# lab1_kozlov_usb_spi.net
KiCad netlist of a schematic drawn in Altium Designer
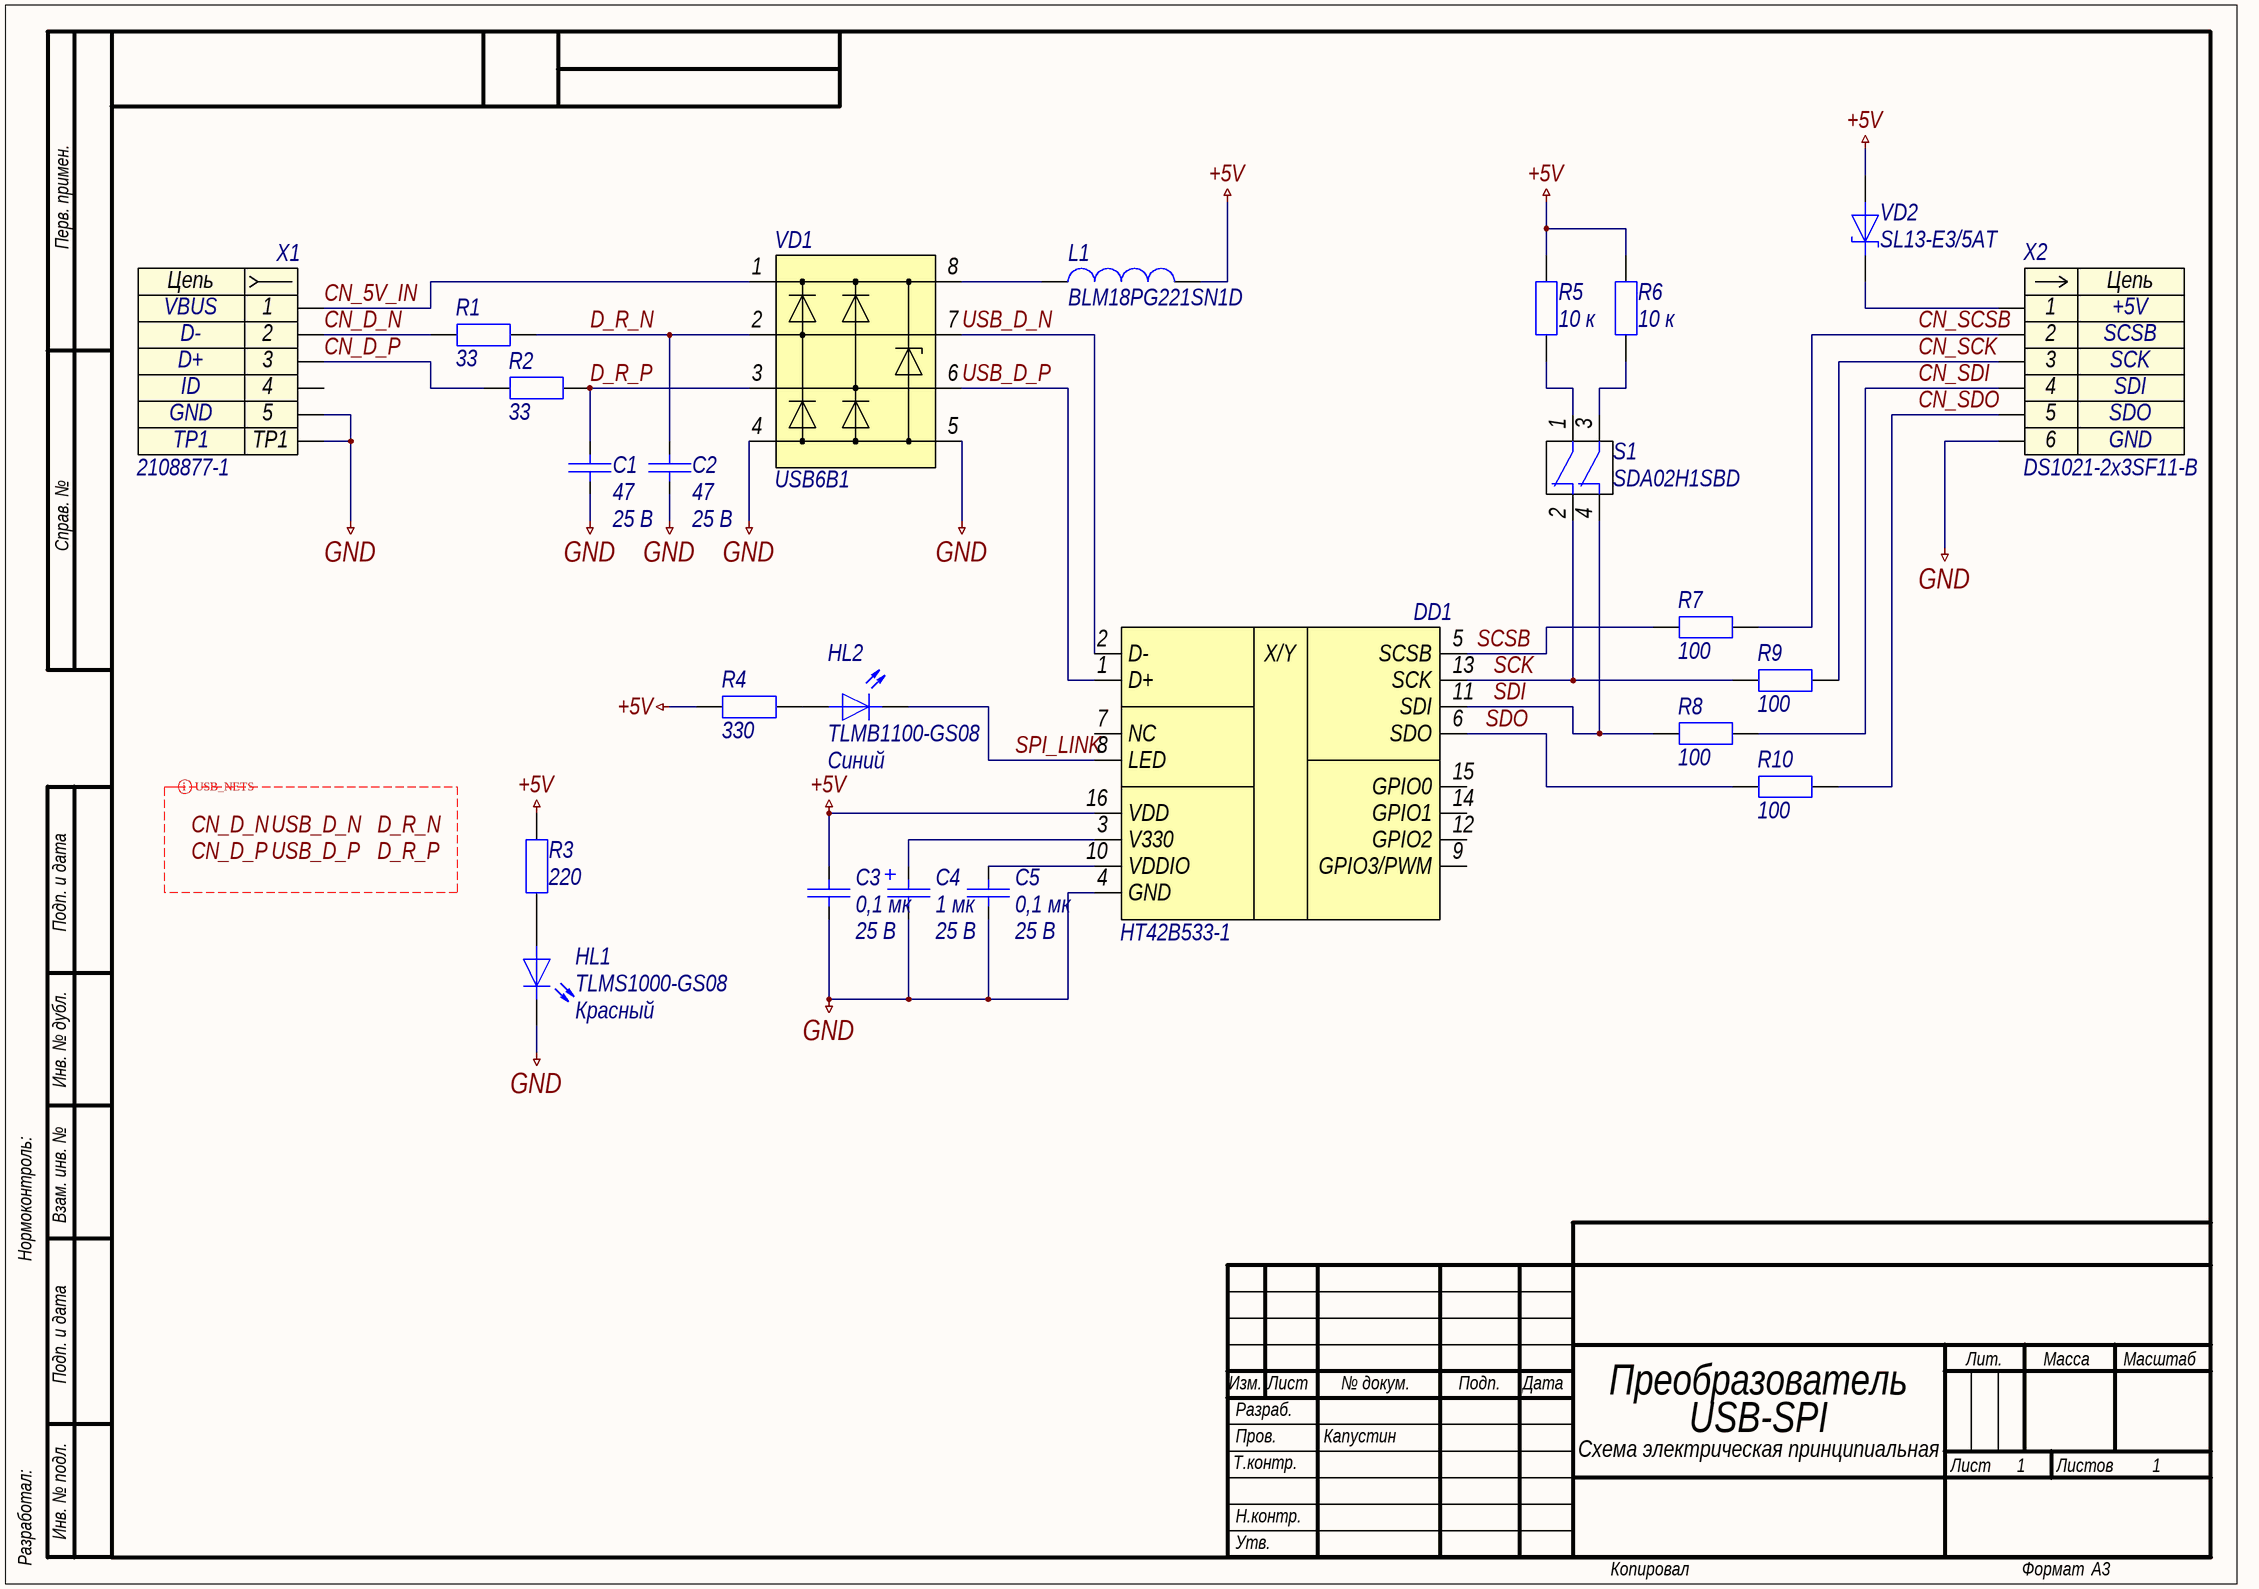
[diagram p0: lab1_kozlov_usb_spi.SchDoc]

(export (version "E")
  (design (tool "Eeschema 10.0.6"))
  (components
    (comp (ref "C1")
      (value "47")
      (footprint "C0201")
      (description "=Описание")
      (fields (field (name "НАПРЯЖЕНИЕ") "25 В"))
      (libsource (lib "Database_Students") (part "CAPACITOR-NONPOLAR"))
    )
    (comp (ref "C2")
      (value "47")
      (footprint "C0201")
      (description "=Описание")
      (fields (field (name "НАПРЯЖЕНИЕ") "25 В"))
      (libsource (lib "Database_Students") (part "CAPACITOR-NONPOLAR"))
    )
    (comp (ref "C3")
      (value "0,1 мк")
      (footprint "C0603")
      (description "=Описание")
      (fields (field (name "НАПРЯЖЕНИЕ") "25 В"))
      (libsource (lib "Database_Students") (part "CAPACITOR-NONPOLAR"))
    )
    (comp (ref "C4")
      (value "1 мк")
      (footprint "C1206POLAR")
      (description "=Описание")
      (fields (field (name "НАПРЯЖЕНИЕ") "25 В"))
      (libsource (lib "Database_Students") (part "CAPACITOR-POLAR"))
    )
    (comp (ref "C5")
      (value "0,1 мк")
      (footprint "C0603")
      (description "=Описание")
      (fields (field (name "НАПРЯЖЕНИЕ") "25 В"))
      (libsource (lib "Database_Students") (part "CAPACITOR-NONPOLAR"))
    )
    (comp (ref "DD1")
      (value "HT42B533-1")
      (footprint "SOP-16")
      (description "=Описание")
      (libsource (lib "Database_Students") (part "HT42B533-1"))
    )
    (comp (ref "HL1")
      (value "TLMS1000-GS08")
      (footprint "HL0603")
      (description "=Описание")
      (fields (field (name "COLOUR") "Красный"))
      (libsource (lib "Database_Students") (part "LED-COMMON"))
    )
    (comp (ref "HL2")
      (value "TLMB1100-GS08")
      (footprint "HL0603")
      (description "=Описание")
      (fields (field (name "COLOUR") "Синий"))
      (libsource (lib "Database_Students") (part "LED-COMMON"))
    )
    (comp (ref "L1")
      (value "BLM18PG221SN1D")
      (footprint "BLM-2-0603")
      (description "=Описание")
      (libsource (lib "Database_Students") (part "FERRITE-BEAD"))
    )
    (comp (ref "R1")
      (value "33")
      (footprint "R0603")
      (description "=Описание")
      (libsource (lib "Database_Students") (part "R-COMMON"))
    )
    (comp (ref "R2")
      (value "33")
      (footprint "R0603")
      (description "=Описание")
      (libsource (lib "Database_Students") (part "R-COMMON"))
    )
    (comp (ref "R3")
      (value "220")
      (footprint "R0603")
      (description "=Описание")
      (libsource (lib "Database_Students") (part "R-COMMON"))
    )
    (comp (ref "R4")
      (value "330")
      (footprint "R0603")
      (description "=Описание")
      (libsource (lib "Database_Students") (part "R-COMMON"))
    )
    (comp (ref "R5")
      (value "10 к")
      (footprint "R0603")
      (description "=Описание")
      (libsource (lib "Database_Students") (part "R-COMMON"))
    )
    (comp (ref "R6")
      (value "10 к")
      (footprint "R0603")
      (description "=Описание")
      (libsource (lib "Database_Students") (part "R-COMMON"))
    )
    (comp (ref "R7")
      (value "100")
      (footprint "R0603")
      (description "=Описание")
      (libsource (lib "Database_Students") (part "R-COMMON"))
    )
    (comp (ref "R8")
      (value "100")
      (footprint "R0603")
      (description "=Описание")
      (libsource (lib "Database_Students") (part "R-COMMON"))
    )
    (comp (ref "R9")
      (value "100")
      (footprint "R0603")
      (description "=Описание")
      (libsource (lib "Database_Students") (part "R-COMMON"))
    )
    (comp (ref "R10")
      (value "100")
      (footprint "R0603")
      (description "=Описание")
      (libsource (lib "Database_Students") (part "R-COMMON"))
    )
    (comp (ref "S1")
      (value "SDA02H1SBD")
      (footprint "SDA02H1SBD")
      (description "=Описание")
      (libsource (lib "Database_Students") (part "SWITCH-4C"))
    )
    (comp (ref "VD1")
      (value "USB6B1")
      (footprint "SOIC-8")
      (description "=Описание")
      (libsource (lib "Database_Students") (part "USB6B1"))
    )
    (comp (ref "VD2")
      (value "SL13-E3/5AT")
      (footprint "DO-214AC")
      (description "=Описание")
      (libsource (lib "Database_Students") (part "DIODE-SCHOTTKY"))
    )
    (comp (ref "X1")
      (value "2108877-1")
      (footprint "2108877-1")
      (description "=Описание")
      (libsource (lib "Database_Students") (part "HEADER-5-TP1-SCT"))
    )
    (comp (ref "X2")
      (value "DS1021-2x3SF11-B")
      (footprint "DS1021-2X3SF11-B")
      (description "=Описание")
      (libsource (lib "Database_Students") (part "HEADER-6-PLG"))
    )
  )
  (nets
    (net (code "1") (name "+5V") (class "Default")
      (node (ref "C3") (pin "1") (pinfunction "1_1") (pintype "passive"))
      (node (ref "DD1") (pin "16") (pinfunction "VDD_16") (pintype "passive"))
      (node (ref "L1") (pin "2") (pinfunction "2_2") (pintype "passive"))
      (node (ref "R3") (pin "2") (pinfunction "2_2") (pintype "passive"))
      (node (ref "R4") (pin "1") (pinfunction "1_1") (pintype "passive"))
      (node (ref "R5") (pin "2") (pinfunction "2_2") (pintype "passive"))
      (node (ref "R6") (pin "2") (pinfunction "2_2") (pintype "passive"))
      (node (ref "VD2") (pin "2") (pinfunction "2_2") (pintype "passive"))
    )
    (net (code "2") (name "/CN_5V_IN") (class "Default")
      (node (ref "VD1") (pin "1") (pinfunction "1_1") (pintype "passive"))
      (node (ref "X1") (pin "1") (pinfunction "1_1") (pintype "passive"))
    )
    (net (code "3") (name "/CN_D_N") (class "Default")
      (node (ref "R1") (pin "1") (pinfunction "1_1") (pintype "passive"))
      (node (ref "X1") (pin "2") (pinfunction "2_2") (pintype "passive"))
    )
    (net (code "4") (name "/CN_D_P") (class "Default")
      (node (ref "R2") (pin "1") (pinfunction "1_1") (pintype "passive"))
      (node (ref "X1") (pin "3") (pinfunction "3_3") (pintype "passive"))
    )
    (net (code "5") (name "/CN_SCK") (class "Default")
      (node (ref "R9") (pin "2") (pinfunction "2_2") (pintype "passive"))
      (node (ref "X2") (pin "3") (pinfunction "3_3") (pintype "passive"))
    )
    (net (code "6") (name "/CN_SCSB") (class "Default")
      (node (ref "R7") (pin "2") (pinfunction "2_2") (pintype "passive"))
      (node (ref "X2") (pin "2") (pinfunction "2_2") (pintype "passive"))
    )
    (net (code "7") (name "/CN_SDI") (class "Default")
      (node (ref "R8") (pin "2") (pinfunction "2_2") (pintype "passive"))
      (node (ref "X2") (pin "4") (pinfunction "4_4") (pintype "passive"))
    )
    (net (code "8") (name "/CN_SDO") (class "Default")
      (node (ref "R10") (pin "2") (pinfunction "2_2") (pintype "passive"))
      (node (ref "X2") (pin "5") (pinfunction "5_5") (pintype "passive"))
    )
    (net (code "9") (name "/D_R_N") (class "Default")
      (node (ref "C2") (pin "1") (pinfunction "1_1") (pintype "passive"))
      (node (ref "R1") (pin "2") (pinfunction "2_2") (pintype "passive"))
      (node (ref "VD1") (pin "2") (pinfunction "2_2") (pintype "passive"))
    )
    (net (code "10") (name "/D_R_P") (class "Default")
      (node (ref "C1") (pin "1") (pinfunction "1_1") (pintype "passive"))
      (node (ref "R2") (pin "2") (pinfunction "2_2") (pintype "passive"))
      (node (ref "VD1") (pin "3") (pinfunction "3_3") (pintype "passive"))
    )
    (net (code "11") (name "/SCK") (class "Default")
      (node (ref "DD1") (pin "13") (pinfunction "SCK_13") (pintype "passive"))
      (node (ref "R9") (pin "1") (pinfunction "1_1") (pintype "passive"))
      (node (ref "S1") (pin "2") (pinfunction "2_2") (pintype "passive"))
    )
    (net (code "12") (name "/SCSB") (class "Default")
      (node (ref "DD1") (pin "5") (pinfunction "SCSB_5") (pintype "passive"))
      (node (ref "R7") (pin "1") (pinfunction "1_1") (pintype "passive"))
    )
    (net (code "13") (name "/SDI") (class "Default")
      (node (ref "DD1") (pin "11") (pinfunction "SDI_11") (pintype "passive"))
      (node (ref "R8") (pin "1") (pinfunction "1_1") (pintype "passive"))
      (node (ref "S1") (pin "4") (pinfunction "4_4") (pintype "passive"))
    )
    (net (code "14") (name "/SDO") (class "Default")
      (node (ref "DD1") (pin "6") (pinfunction "SDO_6") (pintype "passive"))
      (node (ref "R10") (pin "1") (pinfunction "1_1") (pintype "passive"))
    )
    (net (code "15") (name "/SPI_LINK") (class "Default")
      (node (ref "DD1") (pin "8") (pinfunction "LED_8") (pintype "passive"))
      (node (ref "HL2") (pin "1") (pinfunction "1_1") (pintype "passive"))
    )
    (net (code "16") (name "/USB_D_N") (class "Default")
      (node (ref "DD1") (pin "2") (pinfunction "D-_2") (pintype "passive"))
      (node (ref "VD1") (pin "7") (pinfunction "7_7") (pintype "passive"))
    )
    (net (code "17") (name "/USB_D_P") (class "Default")
      (node (ref "DD1") (pin "1") (pinfunction "D+_1") (pintype "passive"))
      (node (ref "VD1") (pin "6") (pinfunction "6_6") (pintype "passive"))
    )
    (net (code "18") (name "GND") (class "Default")
      (node (ref "C1") (pin "2") (pinfunction "2_2") (pintype "passive"))
      (node (ref "C2") (pin "2") (pinfunction "2_2") (pintype "passive"))
      (node (ref "C3") (pin "2") (pinfunction "2_2") (pintype "passive"))
      (node (ref "C4") (pin "2") (pinfunction "2_2") (pintype "passive"))
      (node (ref "C5") (pin "2") (pinfunction "2_2") (pintype "passive"))
      (node (ref "DD1") (pin "4") (pinfunction "GND_4") (pintype "passive"))
      (node (ref "HL1") (pin "1") (pinfunction "1_1") (pintype "passive"))
      (node (ref "VD1") (pin "4") (pinfunction "4_4") (pintype "passive"))
      (node (ref "VD1") (pin "5") (pinfunction "5_5") (pintype "passive"))
      (node (ref "X1") (pin "5") (pinfunction "5_5") (pintype "passive"))
      (node (ref "X1") (pin "TP1") (pinfunction "TP1_TP1") (pintype "passive"))
      (node (ref "X2") (pin "6") (pinfunction "6_6") (pintype "passive"))
    )
    (net (code "19") (name "Net-(DD1-V330)") (class "Default")
      (node (ref "C4") (pin "1") (pinfunction "1_1") (pintype "passive"))
      (node (ref "DD1") (pin "3") (pinfunction "V330_3") (pintype "passive"))
    )
    (net (code "20") (name "Net-(DD1-VDDIO)") (class "Default")
      (node (ref "C5") (pin "1") (pinfunction "1_1") (pintype "passive"))
      (node (ref "DD1") (pin "10") (pinfunction "VDDIO_10") (pintype "passive"))
    )
    (net (code "21") (name "Net-(HL1-Pad2)") (class "Default")
      (node (ref "HL1") (pin "2") (pinfunction "2_2") (pintype "passive"))
      (node (ref "R3") (pin "1") (pinfunction "1_1") (pintype "passive"))
    )
    (net (code "22") (name "Net-(HL2-Pad2)") (class "Default")
      (node (ref "HL2") (pin "2") (pinfunction "2_2") (pintype "passive"))
      (node (ref "R4") (pin "2") (pinfunction "2_2") (pintype "passive"))
    )
    (net (code "23") (name "Net-(L1-Pad1)") (class "Default")
      (node (ref "L1") (pin "1") (pinfunction "1_1") (pintype "passive"))
      (node (ref "VD1") (pin "8") (pinfunction "8_8") (pintype "passive"))
    )
    (net (code "24") (name "Net-(R5-Pad1)") (class "Default")
      (node (ref "R5") (pin "1") (pinfunction "1_1") (pintype "passive"))
      (node (ref "S1") (pin "1") (pinfunction "1_1") (pintype "passive"))
    )
    (net (code "25") (name "Net-(R6-Pad1)") (class "Default")
      (node (ref "R6") (pin "1") (pinfunction "1_1") (pintype "passive"))
      (node (ref "S1") (pin "3") (pinfunction "3_3") (pintype "passive"))
    )
    (net (code "26") (name "Net-(VD2-Pad1)") (class "Default")
      (node (ref "VD2") (pin "1") (pinfunction "1_1") (pintype "passive"))
      (node (ref "X2") (pin "1") (pinfunction "1_1") (pintype "passive"))
    )
    (net (code "27") (name "unconnected-(DD1-GPIO0-Pad15)") (class "Default")
      (node (ref "DD1") (pin "15") (pinfunction "GPIO0_15") (pintype "passive"))
    )
    (net (code "28") (name "unconnected-(DD1-GPIO1-Pad14)") (class "Default")
      (node (ref "DD1") (pin "14") (pinfunction "GPIO1_14") (pintype "passive"))
    )
    (net (code "29") (name "unconnected-(DD1-GPIO2-Pad12)") (class "Default")
      (node (ref "DD1") (pin "12") (pinfunction "GPIO2_12") (pintype "passive"))
    )
    (net (code "30") (name "unconnected-(DD1-GPIO3{slash}PWM-Pad9)") (class "Default")
      (node (ref "DD1") (pin "9") (pinfunction "GPIO3/PWM_9") (pintype "passive"))
    )
    (net (code "31") (name "unconnected-(DD1-NC-Pad7)") (class "Default")
      (node (ref "DD1") (pin "7") (pinfunction "NC_7") (pintype "passive"))
    )
    (net (code "32") (name "unconnected-(X1-Pad4)") (class "Default")
      (node (ref "X1") (pin "4") (pinfunction "4_4") (pintype "passive"))
    )
  )
)
